# ProProject_Magic_wand_2024-10-27.net
KiCad netlist of a schematic drawn in EasyEDA Pro
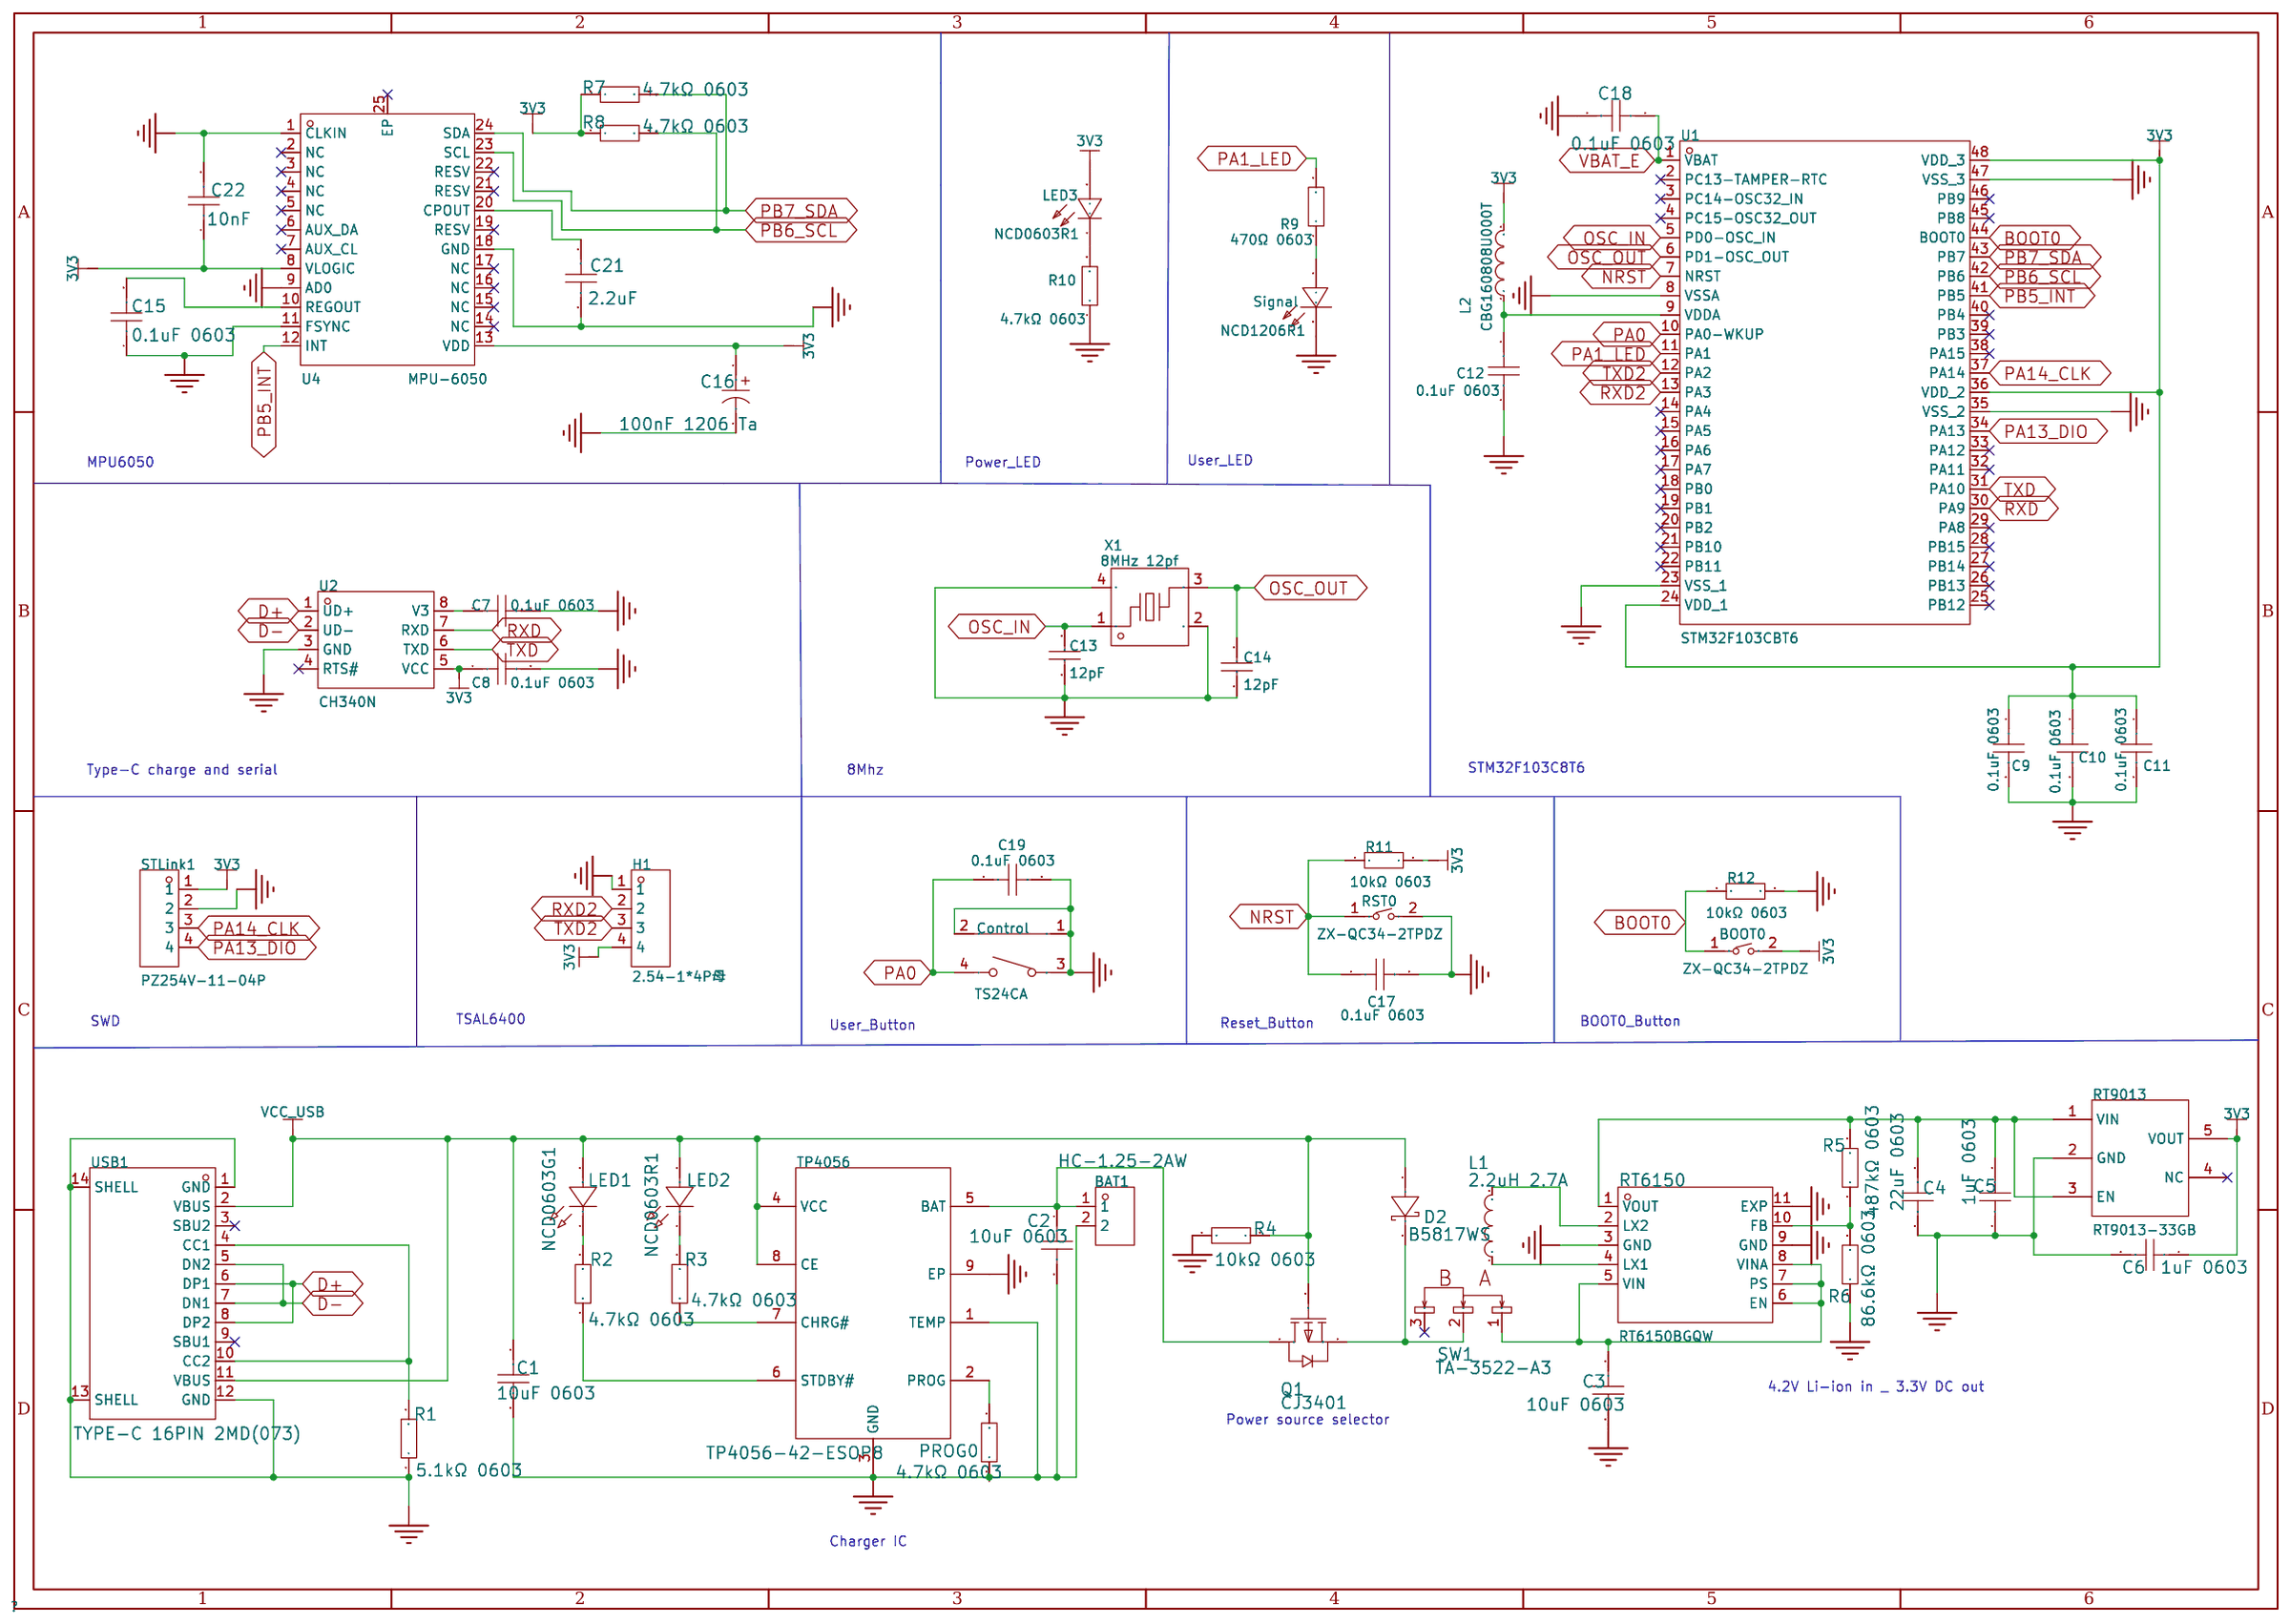
[diagram p0: schematic sheet]

(export (version "E")
  (design (tool "Eeschema 10.0.6"))
  (components
    (comp (ref "BAT1")
      (value "HC-1.25-2AW")
      (footprint "easyedapro:CONN-TH_2P-P1.25_HCTL_HC-1.25-2AW")
      (fields (field (name "Manufacturer") "HCTL(华灿天禄)"))
      (libsource (lib "easyedapro") (part "HC-1.25-2AW"))
    )
    (comp (ref "BOOT0")
      (value "ZX-QC34-2TPDZ")
      (footprint "easyedapro:KEY-SMD_L3.9-W3.0-LS5.0-EH")
      (fields (field (name "Manufacturer") "Megastar(兆星)"))
      (libsource (lib "easyedapro") (part "ZX-QC34-2TPDZ"))
    )
    (comp (ref "C1")
      (value "10uF 0603")
      (footprint "easyedapro:C0603")
      (description "容值:100pF;精度:±5%;额定电压:50V;材质(温度系数):NP0;")
      (fields
        (field (name "Manufacturer Part") "CC0603JRNPO9BN101")
        (field (name "Manufacturer") "YAGEO(国巨)")
      )
      (libsource (lib "easyedapro") (part "CC0603JRNPO9BN101"))
    )
    (comp (ref "C2")
      (value "10uF 0603")
      (footprint "easyedapro:C0603")
      (description "容值:100pF;精度:±5%;额定电压:50V;材质(温度系数):NP0;")
      (fields
        (field (name "Manufacturer Part") "CC0603JRNPO9BN101")
        (field (name "Manufacturer") "YAGEO(国巨)")
      )
      (libsource (lib "easyedapro") (part "CC0603JRNPO9BN101"))
    )
    (comp (ref "C3")
      (value "10uF 0603")
      (footprint "easyedapro:C0603")
      (description "容值:100pF;精度:±5%;额定电压:50V;材质(温度系数):NP0;")
      (fields
        (field (name "Manufacturer Part") "CC0603JRNPO9BN101")
        (field (name "Manufacturer") "YAGEO(国巨)")
      )
      (libsource (lib "easyedapro") (part "CC0603JRNPO9BN101"))
    )
    (comp (ref "C4")
      (value "22uF 0603")
      (footprint "easyedapro:C0603")
      (description "容值:100pF;精度:±5%;额定电压:50V;材质(温度系数):NP0;")
      (fields
        (field (name "Manufacturer Part") "CC0603JRNPO9BN101")
        (field (name "Manufacturer") "YAGEO(国巨)")
      )
      (libsource (lib "easyedapro") (part "CC0603JRNPO9BN101"))
    )
    (comp (ref "C5")
      (value "1uF 0603")
      (footprint "easyedapro:C0603")
      (description "容值:100pF;精度:±5%;额定电压:50V;材质(温度系数):NP0;")
      (fields
        (field (name "Manufacturer Part") "CC0603JRNPO9BN101")
        (field (name "Manufacturer") "YAGEO(国巨)")
      )
      (libsource (lib "easyedapro") (part "CC0603JRNPO9BN101"))
    )
    (comp (ref "C6")
      (value "1uF 0603")
      (footprint "easyedapro:C0603")
      (description "容值:100pF;精度:±5%;额定电压:50V;材质(温度系数):NP0;")
      (fields
        (field (name "Manufacturer Part") "CC0603JRNPO9BN101")
        (field (name "Manufacturer") "YAGEO(国巨)")
      )
      (libsource (lib "easyedapro") (part "CC0603JRNPO9BN101"))
    )
    (comp (ref "C7")
      (value "0.1uF 0603")
      (footprint "easyedapro:C0603")
      (description "容值:100pF;精度:±5%;额定电压:50V;材质(温度系数):NP0;")
      (fields
        (field (name "Manufacturer Part") "CC0603JRNPO9BN101")
        (field (name "Manufacturer") "YAGEO(国巨)")
      )
      (libsource (lib "easyedapro") (part "CC0603JRNPO9BN101"))
    )
    (comp (ref "C8")
      (value "0.1uF 0603")
      (footprint "easyedapro:C0603")
      (description "容值:100pF;精度:±5%;额定电压:50V;材质(温度系数):NP0;")
      (fields
        (field (name "Manufacturer Part") "CC0603JRNPO9BN101")
        (field (name "Manufacturer") "YAGEO(国巨)")
      )
      (libsource (lib "easyedapro") (part "CC0603JRNPO9BN101"))
    )
    (comp (ref "C9")
      (value "0.1uF 0603")
      (footprint "easyedapro:C0603")
      (description "容值:100pF;精度:±5%;额定电压:50V;材质(温度系数):NP0;")
      (fields
        (field (name "Manufacturer Part") "CC0603JRNPO9BN101")
        (field (name "Manufacturer") "YAGEO(国巨)")
      )
      (libsource (lib "easyedapro") (part "CC0603JRNPO9BN101"))
    )
    (comp (ref "C10")
      (value "0.1uF 0603")
      (footprint "easyedapro:C0603")
      (description "容值:100pF;精度:±5%;额定电压:50V;材质(温度系数):NP0;")
      (fields
        (field (name "Manufacturer Part") "CC0603JRNPO9BN101")
        (field (name "Manufacturer") "YAGEO(国巨)")
      )
      (libsource (lib "easyedapro") (part "CC0603JRNPO9BN101"))
    )
    (comp (ref "C11")
      (value "0.1uF 0603")
      (footprint "easyedapro:C0603")
      (description "容值:100pF;精度:±5%;额定电压:50V;材质(温度系数):NP0;")
      (fields
        (field (name "Manufacturer Part") "CC0603JRNPO9BN101")
        (field (name "Manufacturer") "YAGEO(国巨)")
      )
      (libsource (lib "easyedapro") (part "CC0603JRNPO9BN101"))
    )
    (comp (ref "C12")
      (value "0.1uF 0603")
      (footprint "easyedapro:C0603")
      (description "容值:100pF;精度:±5%;额定电压:50V;材质(温度系数):NP0;")
      (fields
        (field (name "Manufacturer Part") "CC0603JRNPO9BN101")
        (field (name "Manufacturer") "YAGEO(国巨)")
      )
      (libsource (lib "easyedapro") (part "CC0603JRNPO9BN101"))
    )
    (comp (ref "C13")
      (value "12pF")
      (footprint "easyedapro:C0603")
      (description "容值:20pF;精度:±5%;额定电压:50V;材质(温度系数):NP0;")
      (fields
        (field (name "Manufacturer Part") "CC0603JRNPO9BN200")
        (field (name "Manufacturer") "YAGEO(国巨)")
      )
      (libsource (lib "easyedapro") (part "CC0603JRNPO9BN200"))
    )
    (comp (ref "C14")
      (value "12pF")
      (footprint "easyedapro:C0603")
      (description "容值:20pF;精度:±5%;额定电压:50V;材质(温度系数):NP0;")
      (fields
        (field (name "Manufacturer Part") "CC0603JRNPO9BN200")
        (field (name "Manufacturer") "YAGEO(国巨)")
      )
      (libsource (lib "easyedapro") (part "CC0603JRNPO9BN200"))
    )
    (comp (ref "C15")
      (value "0.1uF 0603")
      (footprint "easyedapro:C0603")
      (description "容值:100pF;精度:±5%;额定电压:50V;材质(温度系数):NP0;")
      (fields
        (field (name "Manufacturer Part") "CC0603JRNPO9BN101")
        (field (name "Manufacturer") "YAGEO(国巨)")
      )
      (libsource (lib "easyedapro") (part "CC0603JRNPO9BN101"))
    )
    (comp (ref "C16")
      (value "100nF 1206 Ta")
      (footprint "easyedapro:CAP-SMD_L3.2-W1.6-RD")
      (description "容值:100nF;精度:±10%;额定电压:35V;")
      (fields
        (field (name "Manufacturer Part") "CA45-A-35V-0.1UF-K")
        (field (name "Manufacturer") "CEC(振华新云)")
      )
      (libsource (lib "easyedapro") (part "CA45-A-35V-0.1UF-K"))
    )
    (comp (ref "C17")
      (value "0.1uF 0603")
      (footprint "easyedapro:C0603")
      (description "容值:100pF;精度:±5%;额定电压:50V;材质(温度系数):NP0;")
      (fields
        (field (name "Manufacturer Part") "CC0603JRNPO9BN101")
        (field (name "Manufacturer") "YAGEO(国巨)")
      )
      (libsource (lib "easyedapro") (part "CC0603JRNPO9BN101"))
    )
    (comp (ref "C18")
      (value "0.1uF 0603")
      (footprint "easyedapro:C0603")
      (description "容值:100pF;精度:±5%;额定电压:50V;材质(温度系数):NP0;")
      (fields
        (field (name "Manufacturer Part") "CC0603JRNPO9BN101")
        (field (name "Manufacturer") "YAGEO(国巨)")
      )
      (libsource (lib "easyedapro") (part "CC0603JRNPO9BN101"))
    )
    (comp (ref "C19")
      (value "0.1uF 0603")
      (footprint "easyedapro:C0603")
      (description "容值:100pF;精度:±5%;额定电压:50V;材质(温度系数):NP0;")
      (fields
        (field (name "Manufacturer Part") "CC0603JRNPO9BN101")
        (field (name "Manufacturer") "YAGEO(国巨)")
      )
      (libsource (lib "easyedapro") (part "CC0603JRNPO9BN101"))
    )
    (comp (ref "C21")
      (value "2.2uF")
      (footprint "easyedapro:C0603")
      (description "容值:100pF;精度:±5%;额定电压:50V;材质(温度系数):NP0;")
      (fields
        (field (name "Manufacturer Part") "CL10A225KO8NNNC")
        (field (name "Manufacturer") "SAMSUNG(三星)")
      )
      (libsource (lib "easyedapro") (part "CC0603JRNPO9BN101"))
    )
    (comp (ref "C22")
      (value "10nF")
      (footprint "easyedapro:C0603")
      (description "容值:100pF;精度:±5%;额定电压:50V;材质(温度系数):NP0;")
      (fields
        (field (name "Manufacturer Part") "CC0603KRX7R9BB103")
        (field (name "Manufacturer") "YAGEO(国巨)")
      )
      (libsource (lib "easyedapro") (part "CC0603JRNPO9BN101"))
    )
    (comp (ref "Control")
      (value "TS24CA")
      (footprint "easyedapro:SW-SMD_TS24CA")
      (description "电路结构:单刀单掷;按钮形状:矩形按钮;安装方式:卧贴;开关长度:4.55mm;开关宽度:1.8mm;开关高度:3.5mm;触点电流:50mA;额定电压(DC):12V;带灯:-;机械寿命:-;")
      (fields (field (name "Manufacturer") "SHOU HAN(首韩)"))
      (libsource (lib "easyedapro") (part "TS24CA"))
    )
    (comp (ref "D2")
      (value "B5817WS")
      (footprint "easyedapro:SOD-323_L1.7-W1.3-LS2.5-FD")
      (description "二极管配置:独立式;正向压降(Vf):450mV@1.0A;直流反向耐压(Vr):20V;平均整流电流(Io):1A;")
      (fields (field (name "Manufacturer") "宏迦橙"))
      (libsource (lib "easyedapro") (part "B5817WS_C7420329"))
    )
    (comp (ref "H1")
      (value "2.54-1*4P母")
      (footprint "easyedapro:HDR-TH_4P-P2.54-V-F")
      (fields (field (name "Manufacturer") "BOOMELE(博穆精密)"))
      (libsource (lib "easyedapro") (part "2.54-1*4P母"))
    )
    (comp (ref "L1")
      (value "2.2uH 2.7A")
      (footprint "easyedapro:IND-SMD_L2.5-W2.0")
      (description "电感值:2.2uH;精度:±20%;额定电流:2.3A;饱和电流(Isat):2.7A;类型:-;")
      (fields (field (name "Manufacturer Part") "SRN2512-2R2M") (field (name "Manufacturer") "BOURNS"))
      (libsource (lib "easyedapro") (part "SRN2512-2R2M"))
    )
    (comp (ref "L2")
      (value "CBG160808U000T")
      (footprint "easyedapro:L0603")
      (description "标称阻抗@测试频率:0Ω@100MHz;直流电阻(RDC):100mΩ;")
      (fields (field (name "Manufacturer") "FH(风华)"))
      (libsource (lib "easyedapro") (part "CBG160808U000T"))
    )
    (comp (ref "LED1")
      (value "NCD0603G1")
      (fields (field (name "Manufacturer") "国星光电"))
      (libsource (lib "easyedapro") (part "19-219/ghc-yr2t1b5y/3t"))
    )
    (comp (ref "LED2")
      (value "NCD0603R1")
      (fields (field (name "Manufacturer") "国星光电"))
      (libsource (lib "easyedapro") (part "xl-1608surc-06"))
    )
    (comp (ref "LED3")
      (value "NCD0603R1")
      (footprint "easyedapro:LED0603-RD_RED")
      (fields (field (name "Manufacturer") "国星光电"))
      (libsource (lib "easyedapro") (part "FC-DA1608HRK-620D"))
    )
    (comp (ref "PROG0")
      (value "4.7kΩ 0603")
      (footprint "easyedapro:R0603")
      (description "电阻类型:厚膜电阻;阻值:10kΩ;精度:±1%;功率:100mW;最大工作电压:75V;温度系数:±100ppm/°C;")
      (fields
        (field (name "Manufacturer Part") "0603WAF1002T5E")
        (field (name "Manufacturer") "UNI-ROYAL(厚声)")
      )
      (libsource (lib "easyedapro") (part "0603WAF1002T5E"))
    )
    (comp (ref "Q1")
      (value "CJ3401")
      (footprint "easyedapro:SOT-23-3_L2.9-W1.6-P1.90-LS2.8-BR")
      (fields (field (name "Manufacturer") "CJ(江苏长电/长晶)"))
      (libsource (lib "easyedapro") (part "CJ3401"))
    )
    (comp (ref "R1")
      (value "5.1kΩ 0603")
      (footprint "easyedapro:R0603")
      (description "电阻类型:厚膜电阻;阻值:10kΩ;精度:±1%;功率:100mW;最大工作电压:75V;温度系数:±100ppm/°C;")
      (fields
        (field (name "Manufacturer Part") "0603WAF1002T5E")
        (field (name "Manufacturer") "UNI-ROYAL(厚声)")
      )
      (libsource (lib "easyedapro") (part "0603WAF1002T5E"))
    )
    (comp (ref "R2")
      (value "4.7kΩ 0603")
      (footprint "easyedapro:R0603")
      (description "电阻类型:厚膜电阻;阻值:10kΩ;精度:±1%;功率:100mW;最大工作电压:75V;温度系数:±100ppm/°C;")
      (fields
        (field (name "Manufacturer Part") "0603WAF1002T5E")
        (field (name "Manufacturer") "UNI-ROYAL(厚声)")
      )
      (libsource (lib "easyedapro") (part "0603WAF1002T5E"))
    )
    (comp (ref "R3")
      (value "4.7kΩ 0603")
      (footprint "easyedapro:R0603")
      (description "电阻类型:厚膜电阻;阻值:10kΩ;精度:±1%;功率:100mW;最大工作电压:75V;温度系数:±100ppm/°C;")
      (fields
        (field (name "Manufacturer Part") "0603WAF1002T5E")
        (field (name "Manufacturer") "UNI-ROYAL(厚声)")
      )
      (libsource (lib "easyedapro") (part "0603WAF1002T5E"))
    )
    (comp (ref "R4")
      (value "10kΩ 0603")
      (footprint "easyedapro:R0603")
      (description "电阻类型:厚膜电阻;阻值:10kΩ;精度:±1%;功率:100mW;最大工作电压:75V;温度系数:±100ppm/°C;")
      (fields
        (field (name "Manufacturer Part") "0603WAF1002T5E")
        (field (name "Manufacturer") "UNI-ROYAL(厚声)")
      )
      (libsource (lib "easyedapro") (part "0603WAF1002T5E"))
    )
    (comp (ref "R5")
      (value "487kΩ 0603")
      (footprint "easyedapro:R0603")
      (description "电阻类型:厚膜电阻;阻值:10kΩ;精度:±1%;功率:100mW;最大工作电压:75V;温度系数:±100ppm/°C;")
      (fields
        (field (name "Manufacturer Part") "0603WAF1002T5E")
        (field (name "Manufacturer") "UNI-ROYAL(厚声)")
      )
      (libsource (lib "easyedapro") (part "0603WAF1002T5E"))
    )
    (comp (ref "R6")
      (value "86.6kΩ 0603")
      (footprint "easyedapro:R0603")
      (description "电阻类型:厚膜电阻;阻值:10kΩ;精度:±1%;功率:100mW;最大工作电压:75V;温度系数:±100ppm/°C;")
      (fields
        (field (name "Manufacturer Part") "0603WAF1002T5E")
        (field (name "Manufacturer") "UNI-ROYAL(厚声)")
      )
      (libsource (lib "easyedapro") (part "0603WAF1002T5E"))
    )
    (comp (ref "R7")
      (value "4.7kΩ 0603")
      (footprint "easyedapro:R0603")
      (description "电阻类型:厚膜电阻;阻值:10kΩ;精度:±1%;功率:100mW;最大工作电压:75V;温度系数:±100ppm/°C;")
      (fields
        (field (name "Manufacturer Part") "0603WAF1002T5E")
        (field (name "Manufacturer") "UNI-ROYAL(厚声)")
      )
      (libsource (lib "easyedapro") (part "0603WAF1002T5E"))
    )
    (comp (ref "R8")
      (value "4.7kΩ 0603")
      (footprint "easyedapro:R0603")
      (description "电阻类型:厚膜电阻;阻值:10kΩ;精度:±1%;功率:100mW;最大工作电压:75V;温度系数:±100ppm/°C;")
      (fields
        (field (name "Manufacturer Part") "0603WAF1002T5E")
        (field (name "Manufacturer") "UNI-ROYAL(厚声)")
      )
      (libsource (lib "easyedapro") (part "0603WAF1002T5E"))
    )
    (comp (ref "R9")
      (value "470Ω 0603")
      (footprint "easyedapro:R0603")
      (description "电阻类型:厚膜电阻;阻值:10kΩ;精度:±1%;功率:100mW;最大工作电压:75V;温度系数:±100ppm/°C;")
      (fields
        (field (name "Manufacturer Part") "0603WAF1002T5E")
        (field (name "Manufacturer") "UNI-ROYAL(厚声)")
      )
      (libsource (lib "easyedapro") (part "0603WAF1002T5E"))
    )
    (comp (ref "R10")
      (value "4.7kΩ 0603")
      (footprint "easyedapro:R0603")
      (description "电阻类型:厚膜电阻;阻值:10kΩ;精度:±1%;功率:100mW;最大工作电压:75V;温度系数:±100ppm/°C;")
      (fields
        (field (name "Manufacturer Part") "0603WAF1002T5E")
        (field (name "Manufacturer") "UNI-ROYAL(厚声)")
      )
      (libsource (lib "easyedapro") (part "0603WAF1002T5E"))
    )
    (comp (ref "R11")
      (value "10kΩ 0603")
      (footprint "easyedapro:R0603")
      (description "电阻类型:厚膜电阻;阻值:10kΩ;精度:±1%;功率:100mW;最大工作电压:75V;温度系数:±100ppm/°C;")
      (fields
        (field (name "Manufacturer Part") "0603WAF1002T5E")
        (field (name "Manufacturer") "UNI-ROYAL(厚声)")
      )
      (libsource (lib "easyedapro") (part "0603WAF1002T5E"))
    )
    (comp (ref "R12")
      (value "10kΩ 0603")
      (footprint "easyedapro:R0603")
      (description "电阻类型:厚膜电阻;阻值:10kΩ;精度:±1%;功率:100mW;最大工作电压:75V;温度系数:±100ppm/°C;")
      (fields
        (field (name "Manufacturer Part") "0603WAF1002T5E")
        (field (name "Manufacturer") "UNI-ROYAL(厚声)")
      )
      (libsource (lib "easyedapro") (part "0603WAF1002T5E"))
    )
    (comp (ref "RST0")
      (value "ZX-QC34-2TPDZ")
      (footprint "easyedapro:KEY-SMD_L3.9-W3.0-LS5.0-EH")
      (fields (field (name "Manufacturer") "Megastar(兆星)"))
      (libsource (lib "easyedapro") (part "ZX-QC34-2TPDZ"))
    )
    (comp (ref "RT6150")
      (value "RT6150BGQW")
      (footprint "easyedapro:WSON-10_L2.5-W2.5-P0.50-BL-EP")
      (description "功能类型:升降压型;输入电压:1.8V~5.5V;输出电压:1.8V~5.5V;输出电流(最大值):800mA;")
      (fields (field (name "Manufacturer") "RICHTEK(立锜)"))
      (libsource (lib "easyedapro") (part "RT6150BGQW"))
    )
    (comp (ref "RT9013")
      (value "RT9013-33GB")
      (footprint "easyedapro:SOT-23-5_L3.0-W1.7-P0.95-LS2.8-BL")
      (description "输出类型:固定;最大输入电压:5.5V;输出电压:3.3V;最大输出电流:500mA;电源纹波抑制比(PSRR):50dB@(10kHz);输出极性:正极;")
      (fields (field (name "Manufacturer") "RICHTEK(立锜)"))
      (libsource (lib "easyedapro") (part "RT9013-33GB"))
    )
    (comp (ref "Signal")
      (value "NCD1206R1")
      (footprint "easyedapro:LED1206-R-RD_RED")
      (fields (field (name "Manufacturer") "国星光电"))
      (libsource (lib "easyedapro") (part "FC-3215HRK-620D"))
    )
    (comp (ref "STLink1")
      (value "PZ254V-11-04P")
      (footprint "easyedapro:HDR-TH_4P-P2.54-V-M")
      (fields (field (name "Manufacturer") "XFCN(兴飞)"))
      (libsource (lib "easyedapro") (part "PZ254V-11-04P_C2691448"))
    )
    (comp (ref "SW1")
      (value "TA-3522-A3")
      (footprint "easyedapro:SW-TH_3P-L9.1-W3.5-P2.50-A3")
      (fields (field (name "Manufacturer") "Yuandi(元迪)"))
      (libsource (lib "easyedapro") (part "TA-3522-A3"))
    )
    (comp (ref "TP4056")
      (value "TP4056-42-ESOP8")
      (footprint "easyedapro:ESOP-8_L4.9-W3.9-P1.27-LS6.0-BL-EP")
      (description "锂电池充电芯片 42代表电池满电电压4.2V。")
      (fields (field (name "Manufacturer") "TOPPOWER(南京拓微)"))
      (libsource (lib "easyedapro") (part "TP4056"))
    )
    (comp (ref "U1")
      (value "STM32F103CBT6")
      (fields (field (name "Manufacturer") "ST(意法半导体)"))
      (libsource (lib "easyedapro") (part "apm32f103cbt6"))
    )
    (comp (ref "U2")
      (value "CH340N")
      (footprint "easyedapro:SOP-8_L4.9-W3.9-P1.27-LS6.0-BL")
      (fields (field (name "Manufacturer") "WCH(南京沁恒)"))
      (libsource (lib "easyedapro") (part "CH340N_C2977777"))
    )
    (comp (ref "U4")
      (value "MPU-6050")
      (footprint "easyedapro:QFN-24_L4.0-W4.0-P0.50-BL-EP2.7")
      (description "传感器类型:加速度计陀螺仪;")
      (fields (field (name "Manufacturer") "TDK InvenSense(应美盛)"))
      (libsource (lib "easyedapro") (part "MPU-6050_C24112"))
    )
    (comp (ref "USB1")
      (value "TYPE-C 16PIN 2MD(073)")
      (footprint "easyedapro:USB-C-SMD_TYPE-C-6PIN-2MD-073")
      (description "连接器类型:Type-C;标准:-;公母:母;端口数量:1;触点数量:16P;安装方式:卧贴;额定电流 - 电源:5A;工作温度范围:-25°C~+85°C;")
      (fields (field (name "Manufacturer") "SHOU HAN(首韩)"))
      (libsource (lib "easyedapro") (part "TYPE-C 16PIN 2MD(073)"))
    )
    (comp (ref "X1")
      (value "8MHz 12pf")
      (footprint "easyedapro:OSC-SMD_4P-L3.2-W2.5-BL")
      (description "晶振类型:贴片晶振;频率:8MHz;常温频差:±10ppm;外接负载电容:12pF;频率稳定度(全温):±20ppm;")
      (fields (field (name "Manufacturer Part") "X32258MOB4SI") (field (name "Manufacturer") "YXC(扬兴晶振)"))
      (libsource (lib "easyedapro") (part "X32258MOB4SI"))
    )
  )
  (nets
    (net (code "1") (name "3V3") (class "Default")
      (node (ref "BOOT0") (pin "2") (pinfunction "2_2") (pintype "unspecified"))
      (node (ref "C10") (pin "1") (pinfunction "1_1") (pintype "unspecified"))
      (node (ref "C11") (pin "1") (pinfunction "1_1") (pintype "unspecified"))
      (node (ref "C16") (pin "1") (pinfunction "1_1") (pintype "input"))
      (node (ref "C22") (pin "1") (pinfunction "1_1") (pintype "unspecified"))
      (node (ref "C6") (pin "1") (pinfunction "1_1") (pintype "unspecified"))
      (node (ref "C8") (pin "1") (pinfunction "1_1") (pintype "unspecified"))
      (node (ref "C9") (pin "1") (pinfunction "1_1") (pintype "unspecified"))
      (node (ref "H1") (pin "4") (pinfunction "4_4") (pintype "unspecified"))
      (node (ref "L2") (pin "2") (pinfunction "2_2") (pintype "unspecified"))
      (node (ref "LED3") (pin "2") (pinfunction "A_2") (pintype "input"))
      (node (ref "R11") (pin "2") (pinfunction "2_2") (pintype "input"))
      (node (ref "R7") (pin "1") (pinfunction "1_1") (pintype "input"))
      (node (ref "R8") (pin "1") (pinfunction "1_1") (pintype "input"))
      (node (ref "RT9013") (pin "5") (pinfunction "VOUT_5") (pintype "unspecified"))
      (node (ref "STLink1") (pin "1") (pinfunction "1_1") (pintype "unspecified"))
      (node (ref "U1") (pin "24") (pinfunction "VDD_1_24") (pintype "unspecified"))
      (node (ref "U1") (pin "36") (pinfunction "VDD_2_36") (pintype "unspecified"))
      (node (ref "U1") (pin "48") (pinfunction "VDD_3_48") (pintype "unspecified"))
      (node (ref "U2") (pin "5") (pinfunction "VCC_5") (pintype "unspecified"))
      (node (ref "U4") (pin "13") (pinfunction "VDD_13") (pintype "unspecified"))
      (node (ref "U4") (pin "8") (pinfunction "VLOGIC_8") (pintype "unspecified"))
    )
    (net (code "2") (name "BOOT0") (class "Default")
      (node (ref "BOOT0") (pin "1") (pinfunction "1_1") (pintype "unspecified"))
      (node (ref "R12") (pin "1") (pinfunction "1_1") (pintype "input"))
      (node (ref "U1") (pin "44") (pinfunction "BOOT0_44") (pintype "unspecified"))
    )
    (net (code "3") (name "D+") (class "Default")
      (node (ref "U2") (pin "1") (pinfunction "UD+_1") (pintype "unspecified"))
      (node (ref "USB1") (pin "6") (pinfunction "DP1_6") (pintype "unspecified"))
      (node (ref "USB1") (pin "8") (pinfunction "DP2_8") (pintype "unspecified"))
    )
    (net (code "4") (name "D-") (class "Default")
      (node (ref "U2") (pin "2") (pinfunction "UD-_2") (pintype "unspecified"))
      (node (ref "USB1") (pin "5") (pinfunction "DN2_5") (pintype "unspecified"))
      (node (ref "USB1") (pin "7") (pinfunction "DN1_7") (pintype "unspecified"))
    )
    (net (code "5") (name "GND") (class "Default")
      (node (ref "BAT1") (pin "2") (pinfunction "2_2") (pintype "unspecified"))
      (node (ref "C1") (pin "2") (pinfunction "2_2") (pintype "unspecified"))
      (node (ref "C10") (pin "2") (pinfunction "2_2") (pintype "unspecified"))
      (node (ref "C11") (pin "2") (pinfunction "2_2") (pintype "unspecified"))
      (node (ref "C12") (pin "1") (pinfunction "1_1") (pintype "unspecified"))
      (node (ref "C13") (pin "1") (pinfunction "1_1") (pintype "input"))
      (node (ref "C14") (pin "1") (pinfunction "1_1") (pintype "input"))
      (node (ref "C15") (pin "1") (pinfunction "1_1") (pintype "unspecified"))
      (node (ref "C16") (pin "2") (pinfunction "2_2") (pintype "input"))
      (node (ref "C17") (pin "2") (pinfunction "2_2") (pintype "unspecified"))
      (node (ref "C18") (pin "2") (pinfunction "2_2") (pintype "unspecified"))
      (node (ref "C19") (pin "2") (pinfunction "2_2") (pintype "unspecified"))
      (node (ref "C2") (pin "2") (pinfunction "2_2") (pintype "unspecified"))
      (node (ref "C21") (pin "2") (pinfunction "2_2") (pintype "unspecified"))
      (node (ref "C22") (pin "2") (pinfunction "2_2") (pintype "unspecified"))
      (node (ref "C3") (pin "2") (pinfunction "2_2") (pintype "unspecified"))
      (node (ref "C4") (pin "2") (pinfunction "2_2") (pintype "unspecified"))
      (node (ref "C5") (pin "2") (pinfunction "2_2") (pintype "unspecified"))
      (node (ref "C6") (pin "2") (pinfunction "2_2") (pintype "unspecified"))
      (node (ref "C7") (pin "2") (pinfunction "2_2") (pintype "unspecified"))
      (node (ref "C8") (pin "2") (pinfunction "2_2") (pintype "unspecified"))
      (node (ref "C9") (pin "2") (pinfunction "2_2") (pintype "unspecified"))
      (node (ref "Control") (pin "1") (pinfunction "1_1") (pintype "input"))
      (node (ref "Control") (pin "2") (pinfunction "2_2") (pintype "input"))
      (node (ref "Control") (pin "3") (pinfunction "3_3") (pintype "input"))
      (node (ref "H1") (pin "1") (pinfunction "1_1") (pintype "unspecified"))
      (node (ref "PROG0") (pin "1") (pinfunction "1_1") (pintype "input"))
      (node (ref "R1") (pin "1") (pinfunction "1_1") (pintype "input"))
      (node (ref "R10") (pin "1") (pinfunction "1_1") (pintype "input"))
      (node (ref "R12") (pin "2") (pinfunction "2_2") (pintype "input"))
      (node (ref "R4") (pin "2") (pinfunction "2_2") (pintype "input"))
      (node (ref "R6") (pin "1") (pinfunction "1_1") (pintype "input"))
      (node (ref "RST0") (pin "2") (pinfunction "2_2") (pintype "unspecified"))
      (node (ref "RT6150") (pin "11") (pinfunction "EXP_11") (pintype "input"))
      (node (ref "RT6150") (pin "3") (pinfunction "GND_3") (pintype "input"))
      (node (ref "RT6150") (pin "9") (pinfunction "GND_9") (pintype "input"))
      (node (ref "RT9013") (pin "2") (pinfunction "GND_2") (pintype "unspecified"))
      (node (ref "STLink1") (pin "2") (pinfunction "2_2") (pintype "unspecified"))
      (node (ref "Signal") (pin "2") (pinfunction "K_2") (pintype "unspecified"))
      (node (ref "TP4056") (pin "1") (pinfunction "TEMP_1") (pintype "unspecified"))
      (node (ref "TP4056") (pin "3") (pinfunction "GND_3") (pintype "unspecified"))
      (node (ref "TP4056") (pin "9") (pinfunction "EP_9") (pintype "unspecified"))
      (node (ref "U1") (pin "23") (pinfunction "VSS_1_23") (pintype "unspecified"))
      (node (ref "U1") (pin "35") (pinfunction "VSS_2_35") (pintype "unspecified"))
      (node (ref "U1") (pin "47") (pinfunction "VSS_3_47") (pintype "unspecified"))
      (node (ref "U1") (pin "8") (pinfunction "VSSA_8") (pintype "unspecified"))
      (node (ref "U2") (pin "3") (pinfunction "GND_3") (pintype "unspecified"))
      (node (ref "U4") (pin "1") (pinfunction "CLKIN_1") (pintype "unspecified"))
      (node (ref "U4") (pin "11") (pinfunction "FSYNC_11") (pintype "unspecified"))
      (node (ref "U4") (pin "18") (pinfunction "GND_18") (pintype "unspecified"))
      (node (ref "U4") (pin "9") (pinfunction "AD0_9") (pintype "unspecified"))
      (node (ref "USB1") (pin "1") (pinfunction "GND_1") (pintype "unspecified"))
      (node (ref "USB1") (pin "12") (pinfunction "GND_12") (pintype "unspecified"))
      (node (ref "USB1") (pin "13") (pinfunction "SHELL_13") (pintype "unspecified"))
      (node (ref "USB1") (pin "14") (pinfunction "SHELL_14") (pintype "unspecified"))
      (node (ref "X1") (pin "2") (pinfunction "GND_2") (pintype "input"))
      (node (ref "X1") (pin "4") (pinfunction "GND_4") (pintype "input"))
    )
    (net (code "6") (name "NRST") (class "Default")
      (node (ref "C17") (pin "1") (pinfunction "1_1") (pintype "unspecified"))
      (node (ref "R11") (pin "1") (pinfunction "1_1") (pintype "input"))
      (node (ref "RST0") (pin "1") (pinfunction "1_1") (pintype "unspecified"))
      (node (ref "U1") (pin "7") (pinfunction "NRST_7") (pintype "unspecified"))
    )
    (net (code "7") (name "Net-(D2-K)") (class "Default")
      (node (ref "D2") (pin "2") (pinfunction "K_2") (pintype "unspecified"))
      (node (ref "Q1") (pin "2") (pinfunction "S_2") (pintype "unspecified"))
      (node (ref "SW1") (pin "2") (pinfunction "2_2") (pintype "unspecified"))
    )
    (net (code "8") (name "Net-(LED1-K)") (class "Default")
      (node (ref "LED1") (pin "1") (pinfunction "K_1") (pintype "unspecified"))
      (node (ref "R2") (pin "2") (pinfunction "2_2") (pintype "input"))
    )
    (net (code "9") (name "Net-(LED2-K)") (class "Default")
      (node (ref "LED2") (pin "1") (pinfunction "K_1") (pintype "unspecified"))
      (node (ref "R3") (pin "2") (pinfunction "2_2") (pintype "input"))
    )
    (net (code "10") (name "Net-(LED3-K)") (class "Default")
      (node (ref "LED3") (pin "1") (pinfunction "K_1") (pintype "input"))
      (node (ref "R10") (pin "2") (pinfunction "2_2") (pintype "input"))
    )
    (net (code "11") (name "Net-(Q1-D)") (class "Default")
      (node (ref "BAT1") (pin "1") (pinfunction "1_1") (pintype "unspecified"))
      (node (ref "C2") (pin "1") (pinfunction "1_1") (pintype "unspecified"))
      (node (ref "Q1") (pin "3") (pinfunction "D_3") (pintype "unspecified"))
      (node (ref "TP4056") (pin "5") (pinfunction "BAT_5") (pintype "unspecified"))
    )
    (net (code "12") (name "Net-(RT6150-EN)") (class "Default")
      (node (ref "C3") (pin "1") (pinfunction "1_1") (pintype "unspecified"))
      (node (ref "RT6150") (pin "5") (pinfunction "VIN_5") (pintype "input"))
      (node (ref "RT6150") (pin "6") (pinfunction "EN_6") (pintype "input"))
      (node (ref "RT6150") (pin "7") (pinfunction "PS_7") (pintype "input"))
      (node (ref "RT6150") (pin "8") (pinfunction "VINA_8") (pintype "input"))
      (node (ref "SW1") (pin "1") (pinfunction "1_1") (pintype "unspecified"))
    )
    (net (code "13") (name "Net-(RT6150-FB)") (class "Default")
      (node (ref "R5") (pin "1") (pinfunction "1_1") (pintype "input"))
      (node (ref "R6") (pin "2") (pinfunction "2_2") (pintype "input"))
      (node (ref "RT6150") (pin "10") (pinfunction "FB_10") (pintype "input"))
    )
    (net (code "14") (name "Net-(RT6150-LX1)") (class "Default")
      (node (ref "L1") (pin "1") (pinfunction "1_1") (pintype "input"))
      (node (ref "RT6150") (pin "4") (pinfunction "LX1_4") (pintype "input"))
    )
    (net (code "15") (name "Net-(RT6150-LX2)") (class "Default")
      (node (ref "L1") (pin "2") (pinfunction "2_2") (pintype "input"))
      (node (ref "RT6150") (pin "2") (pinfunction "LX2_2") (pintype "input"))
    )
    (net (code "16") (name "Net-(RT6150-VOUT)") (class "Default")
      (node (ref "C4") (pin "1") (pinfunction "1_1") (pintype "unspecified"))
      (node (ref "C5") (pin "1") (pinfunction "1_1") (pintype "unspecified"))
      (node (ref "R5") (pin "2") (pinfunction "2_2") (pintype "input"))
      (node (ref "RT6150") (pin "1") (pinfunction "VOUT_1") (pintype "input"))
      (node (ref "RT9013") (pin "1") (pinfunction "VIN_1") (pintype "unspecified"))
      (node (ref "RT9013") (pin "3") (pinfunction "EN_3") (pintype "unspecified"))
    )
    (net (code "17") (name "Net-(Signal-A)") (class "Default")
      (node (ref "R9") (pin "1") (pinfunction "1_1") (pintype "input"))
      (node (ref "Signal") (pin "1") (pinfunction "A_1") (pintype "unspecified"))
    )
    (net (code "18") (name "Net-(TP4056-CHRG#)") (class "Default")
      (node (ref "R3") (pin "1") (pinfunction "1_1") (pintype "input"))
      (node (ref "TP4056") (pin "7") (pinfunction "CHRG#_7") (pintype "unspecified"))
    )
    (net (code "19") (name "Net-(TP4056-PROG)") (class "Default")
      (node (ref "PROG0") (pin "2") (pinfunction "2_2") (pintype "input"))
      (node (ref "TP4056") (pin "2") (pinfunction "PROG_2") (pintype "unspecified"))
    )
    (net (code "20") (name "Net-(TP4056-STDBY#)") (class "Default")
      (node (ref "R2") (pin "1") (pinfunction "1_1") (pintype "input"))
      (node (ref "TP4056") (pin "6") (pinfunction "STDBY#_6") (pintype "unspecified"))
    )
    (net (code "21") (name "Net-(U1-VDDA)") (class "Default")
      (node (ref "C12") (pin "2") (pinfunction "2_2") (pintype "unspecified"))
      (node (ref "L2") (pin "1") (pinfunction "1_1") (pintype "unspecified"))
      (node (ref "U1") (pin "9") (pinfunction "VDDA_9") (pintype "unspecified"))
    )
    (net (code "22") (name "Net-(U2-V3)") (class "Default")
      (node (ref "C7") (pin "1") (pinfunction "1_1") (pintype "unspecified"))
      (node (ref "U2") (pin "8") (pinfunction "V3_8") (pintype "unspecified"))
    )
    (net (code "23") (name "Net-(U4-CPOUT)") (class "Default")
      (node (ref "C21") (pin "1") (pinfunction "1_1") (pintype "unspecified"))
      (node (ref "U4") (pin "20") (pinfunction "CPOUT_20") (pintype "unspecified"))
    )
    (net (code "24") (name "Net-(U4-REGOUT)") (class "Default")
      (node (ref "C15") (pin "2") (pinfunction "2_2") (pintype "unspecified"))
      (node (ref "U4") (pin "10") (pinfunction "REGOUT_10") (pintype "unspecified"))
    )
    (net (code "25") (name "Net-(USB1-CC1)") (class "Default")
      (node (ref "R1") (pin "2") (pinfunction "2_2") (pintype "input"))
      (node (ref "USB1") (pin "10") (pinfunction "CC2_10") (pintype "unspecified"))
      (node (ref "USB1") (pin "4") (pinfunction "CC1_4") (pintype "unspecified"))
    )
    (net (code "26") (name "OSC_IN") (class "Default")
      (node (ref "C13") (pin "2") (pinfunction "2_2") (pintype "input"))
      (node (ref "U1") (pin "5") (pinfunction "PD0-OSC_IN_5") (pintype "unspecified"))
      (node (ref "X1") (pin "1") (pinfunction "1_1") (pintype "input"))
    )
    (net (code "27") (name "OSC_OUT") (class "Default")
      (node (ref "C14") (pin "2") (pinfunction "2_2") (pintype "input"))
      (node (ref "U1") (pin "6") (pinfunction "PD1-OSC_OUT_6") (pintype "unspecified"))
      (node (ref "X1") (pin "3") (pinfunction "3_3") (pintype "input"))
    )
    (net (code "28") (name "PA0") (class "Default")
      (node (ref "C19") (pin "1") (pinfunction "1_1") (pintype "unspecified"))
      (node (ref "Control") (pin "4") (pinfunction "4_4") (pintype "input"))
      (node (ref "U1") (pin "10") (pinfunction "PA0-WKUP_10") (pintype "unspecified"))
    )
    (net (code "29") (name "PA1_LED") (class "Default")
      (node (ref "R9") (pin "2") (pinfunction "2_2") (pintype "input"))
      (node (ref "U1") (pin "11") (pinfunction "PA1_11") (pintype "unspecified"))
    )
    (net (code "30") (name "PA13_DIO") (class "Default")
      (node (ref "STLink1") (pin "4") (pinfunction "4_4") (pintype "unspecified"))
      (node (ref "U1") (pin "34") (pinfunction "PA13_34") (pintype "unspecified"))
    )
    (net (code "31") (name "PA14_CLK") (class "Default")
      (node (ref "STLink1") (pin "3") (pinfunction "3_3") (pintype "unspecified"))
      (node (ref "U1") (pin "37") (pinfunction "PA14_37") (pintype "unspecified"))
    )
    (net (code "32") (name "PB5_INT") (class "Default")
      (node (ref "U1") (pin "41") (pinfunction "PB5_41") (pintype "unspecified"))
      (node (ref "U4") (pin "12") (pinfunction "INT_12") (pintype "unspecified"))
    )
    (net (code "33") (name "PB6_SCL") (class "Default")
      (node (ref "R8") (pin "2") (pinfunction "2_2") (pintype "input"))
      (node (ref "U1") (pin "42") (pinfunction "PB6_42") (pintype "unspecified"))
      (node (ref "U4") (pin "23") (pinfunction "SCL_23") (pintype "unspecified"))
    )
    (net (code "34") (name "PB7_SDA") (class "Default")
      (node (ref "R7") (pin "2") (pinfunction "2_2") (pintype "input"))
      (node (ref "U1") (pin "43") (pinfunction "PB7_43") (pintype "unspecified"))
      (node (ref "U4") (pin "24") (pinfunction "SDA_24") (pintype "unspecified"))
    )
    (net (code "35") (name "RXD") (class "Default")
      (node (ref "U1") (pin "30") (pinfunction "PA9_30") (pintype "unspecified"))
      (node (ref "U2") (pin "7") (pinfunction "RXD_7") (pintype "unspecified"))
    )
    (net (code "36") (name "RXD2") (class "Default")
      (node (ref "H1") (pin "2") (pinfunction "2_2") (pintype "unspecified"))
      (node (ref "U1") (pin "13") (pinfunction "PA3_13") (pintype "unspecified"))
    )
    (net (code "37") (name "TXD") (class "Default")
      (node (ref "U1") (pin "31") (pinfunction "PA10_31") (pintype "unspecified"))
      (node (ref "U2") (pin "6") (pinfunction "TXD_6") (pintype "unspecified"))
    )
    (net (code "38") (name "TXD2") (class "Default")
      (node (ref "H1") (pin "3") (pinfunction "3_3") (pintype "unspecified"))
      (node (ref "U1") (pin "12") (pinfunction "PA2_12") (pintype "unspecified"))
    )
    (net (code "39") (name "VBAT_E") (class "Default")
      (node (ref "C18") (pin "1") (pinfunction "1_1") (pintype "unspecified"))
      (node (ref "U1") (pin "1") (pinfunction "VBAT_1") (pintype "unspecified"))
    )
    (net (code "40") (name "VCC_USB") (class "Default")
      (node (ref "C1") (pin "1") (pinfunction "1_1") (pintype "unspecified"))
      (node (ref "D2") (pin "1") (pinfunction "A_1") (pintype "unspecified"))
      (node (ref "LED1") (pin "2") (pinfunction "A_2") (pintype "unspecified"))
      (node (ref "LED2") (pin "2") (pinfunction "A_2") (pintype "unspecified"))
      (node (ref "Q1") (pin "1") (pinfunction "G_1") (pintype "unspecified"))
      (node (ref "R4") (pin "1") (pinfunction "1_1") (pintype "input"))
      (node (ref "TP4056") (pin "4") (pinfunction "VCC_4") (pintype "unspecified"))
      (node (ref "TP4056") (pin "8") (pinfunction "CE_8") (pintype "unspecified"))
      (node (ref "USB1") (pin "11") (pinfunction "VBUS_11") (pintype "unspecified"))
      (node (ref "USB1") (pin "2") (pinfunction "VBUS_2") (pintype "unspecified"))
    )
    (net (code "41") (name "unconnected-(RT9013-NC-Pad4)") (class "Default")
      (node (ref "RT9013") (pin "4") (pinfunction "NC_4") (pintype "unspecified+no_connect"))
    )
    (net (code "42") (name "unconnected-(SW1-Pad3)") (class "Default")
      (node (ref "SW1") (pin "3") (pinfunction "3_3") (pintype "unspecified+no_connect"))
    )
    (net (code "43") (name "unconnected-(U1-PA4-Pad14)") (class "Default")
      (node (ref "U1") (pin "14") (pinfunction "PA4_14") (pintype "unspecified+no_connect"))
    )
    (net (code "44") (name "unconnected-(U1-PA5-Pad15)") (class "Default")
      (node (ref "U1") (pin "15") (pinfunction "PA5_15") (pintype "unspecified+no_connect"))
    )
    (net (code "45") (name "unconnected-(U1-PA6-Pad16)") (class "Default")
      (node (ref "U1") (pin "16") (pinfunction "PA6_16") (pintype "unspecified+no_connect"))
    )
    (net (code "46") (name "unconnected-(U1-PA7-Pad17)") (class "Default")
      (node (ref "U1") (pin "17") (pinfunction "PA7_17") (pintype "unspecified+no_connect"))
    )
    (net (code "47") (name "unconnected-(U1-PA8-Pad29)") (class "Default")
      (node (ref "U1") (pin "29") (pinfunction "PA8_29") (pintype "unspecified+no_connect"))
    )
    (net (code "48") (name "unconnected-(U1-PA11-Pad32)") (class "Default")
      (node (ref "U1") (pin "32") (pinfunction "PA11_32") (pintype "unspecified+no_connect"))
    )
    (net (code "49") (name "unconnected-(U1-PA12-Pad33)") (class "Default")
      (node (ref "U1") (pin "33") (pinfunction "PA12_33") (pintype "unspecified+no_connect"))
    )
    (net (code "50") (name "unconnected-(U1-PA15-Pad38)") (class "Default")
      (node (ref "U1") (pin "38") (pinfunction "PA15_38") (pintype "unspecified+no_connect"))
    )
    (net (code "51") (name "unconnected-(U1-PB0-Pad18)") (class "Default")
      (node (ref "U1") (pin "18") (pinfunction "PB0_18") (pintype "unspecified+no_connect"))
    )
    (net (code "52") (name "unconnected-(U1-PB1-Pad19)") (class "Default")
      (node (ref "U1") (pin "19") (pinfunction "PB1_19") (pintype "unspecified+no_connect"))
    )
    (net (code "53") (name "unconnected-(U1-PB2-Pad20)") (class "Default")
      (node (ref "U1") (pin "20") (pinfunction "PB2_20") (pintype "unspecified+no_connect"))
    )
    (net (code "54") (name "unconnected-(U1-PB3-Pad39)") (class "Default")
      (node (ref "U1") (pin "39") (pinfunction "PB3_39") (pintype "unspecified+no_connect"))
    )
    (net (code "55") (name "unconnected-(U1-PB4-Pad40)") (class "Default")
      (node (ref "U1") (pin "40") (pinfunction "PB4_40") (pintype "unspecified+no_connect"))
    )
    (net (code "56") (name "unconnected-(U1-PB8-Pad45)") (class "Default")
      (node (ref "U1") (pin "45") (pinfunction "PB8_45") (pintype "unspecified+no_connect"))
    )
    (net (code "57") (name "unconnected-(U1-PB9-Pad46)") (class "Default")
      (node (ref "U1") (pin "46") (pinfunction "PB9_46") (pintype "unspecified+no_connect"))
    )
    (net (code "58") (name "unconnected-(U1-PB10-Pad21)") (class "Default")
      (node (ref "U1") (pin "21") (pinfunction "PB10_21") (pintype "unspecified+no_connect"))
    )
    (net (code "59") (name "unconnected-(U1-PB11-Pad22)") (class "Default")
      (node (ref "U1") (pin "22") (pinfunction "PB11_22") (pintype "unspecified+no_connect"))
    )
    (net (code "60") (name "unconnected-(U1-PB12-Pad25)") (class "Default")
      (node (ref "U1") (pin "25") (pinfunction "PB12_25") (pintype "unspecified+no_connect"))
    )
    (net (code "61") (name "unconnected-(U1-PB13-Pad26)") (class "Default")
      (node (ref "U1") (pin "26") (pinfunction "PB13_26") (pintype "unspecified+no_connect"))
    )
    (net (code "62") (name "unconnected-(U1-PB14-Pad27)") (class "Default")
      (node (ref "U1") (pin "27") (pinfunction "PB14_27") (pintype "unspecified+no_connect"))
    )
    (net (code "63") (name "unconnected-(U1-PB15-Pad28)") (class "Default")
      (node (ref "U1") (pin "28") (pinfunction "PB15_28") (pintype "unspecified+no_connect"))
    )
    (net (code "64") (name "unconnected-(U1-PC13-TAMPER-RTC-Pad2)") (class "Default")
      (node (ref "U1") (pin "2") (pinfunction "PC13-TAMPER-RTC_2") (pintype "unspecified+no_connect"))
    )
    (net (code "65") (name "unconnected-(U1-PC14-OSC32_IN-Pad3)") (class "Default")
      (node (ref "U1") (pin "3") (pinfunction "PC14-OSC32_IN_3") (pintype "unspecified+no_connect"))
    )
    (net (code "66") (name "unconnected-(U1-PC15-OSC32_OUT-Pad4)") (class "Default")
      (node (ref "U1") (pin "4") (pinfunction "PC15-OSC32_OUT_4") (pintype "unspecified+no_connect"))
    )
    (net (code "67") (name "unconnected-(U2-RTS#-Pad4)") (class "Default")
      (node (ref "U2") (pin "4") (pinfunction "RTS#_4") (pintype "unspecified+no_connect"))
    )
    (net (code "68") (name "unconnected-(U4-AUX_CL-Pad7)") (class "Default")
      (node (ref "U4") (pin "7") (pinfunction "AUX_CL_7") (pintype "unspecified+no_connect"))
    )
    (net (code "69") (name "unconnected-(U4-AUX_DA-Pad6)") (class "Default")
      (node (ref "U4") (pin "6") (pinfunction "AUX_DA_6") (pintype "unspecified+no_connect"))
    )
    (net (code "70") (name "unconnected-(U4-EP-Pad25)") (class "Default")
      (node (ref "U4") (pin "25") (pinfunction "EP_25") (pintype "unspecified+no_connect"))
    )
    (net (code "71") (name "unconnected-(U4-NC-Pad2)") (class "Default")
      (node (ref "U4") (pin "2") (pinfunction "NC_2") (pintype "unspecified+no_connect"))
    )
    (net (code "72") (name "unconnected-(U4-NC-Pad3)") (class "Default")
      (node (ref "U4") (pin "3") (pinfunction "NC_3") (pintype "unspecified+no_connect"))
    )
    (net (code "73") (name "unconnected-(U4-NC-Pad4)") (class "Default")
      (node (ref "U4") (pin "4") (pinfunction "NC_4") (pintype "unspecified+no_connect"))
    )
    (net (code "74") (name "unconnected-(U4-NC-Pad5)") (class "Default")
      (node (ref "U4") (pin "5") (pinfunction "NC_5") (pintype "unspecified+no_connect"))
    )
    (net (code "75") (name "unconnected-(U4-NC-Pad14)") (class "Default")
      (node (ref "U4") (pin "14") (pinfunction "NC_14") (pintype "unspecified+no_connect"))
    )
    (net (code "76") (name "unconnected-(U4-NC-Pad15)") (class "Default")
      (node (ref "U4") (pin "15") (pinfunction "NC_15") (pintype "unspecified+no_connect"))
    )
    (net (code "77") (name "unconnected-(U4-NC-Pad16)") (class "Default")
      (node (ref "U4") (pin "16") (pinfunction "NC_16") (pintype "unspecified+no_connect"))
    )
    (net (code "78") (name "unconnected-(U4-NC-Pad17)") (class "Default")
      (node (ref "U4") (pin "17") (pinfunction "NC_17") (pintype "unspecified+no_connect"))
    )
    (net (code "79") (name "unconnected-(U4-RESV-Pad19)") (class "Default")
      (node (ref "U4") (pin "19") (pinfunction "RESV_19") (pintype "unspecified+no_connect"))
    )
    (net (code "80") (name "unconnected-(U4-RESV-Pad21)") (class "Default")
      (node (ref "U4") (pin "21") (pinfunction "RESV_21") (pintype "unspecified+no_connect"))
    )
    (net (code "81") (name "unconnected-(U4-RESV-Pad22)") (class "Default")
      (node (ref "U4") (pin "22") (pinfunction "RESV_22") (pintype "unspecified+no_connect"))
    )
    (net (code "82") (name "unconnected-(USB1-SBU1-Pad9)") (class "Default")
      (node (ref "USB1") (pin "9") (pinfunction "SBU1_9") (pintype "unspecified+no_connect"))
    )
    (net (code "83") (name "unconnected-(USB1-SBU2-Pad3)") (class "Default")
      (node (ref "USB1") (pin "3") (pinfunction "SBU2_3") (pintype "unspecified+no_connect"))
    )
  )
)
